# console_schematic_logic.net
KiCad netlist of a schematic drawn in Altium Designer
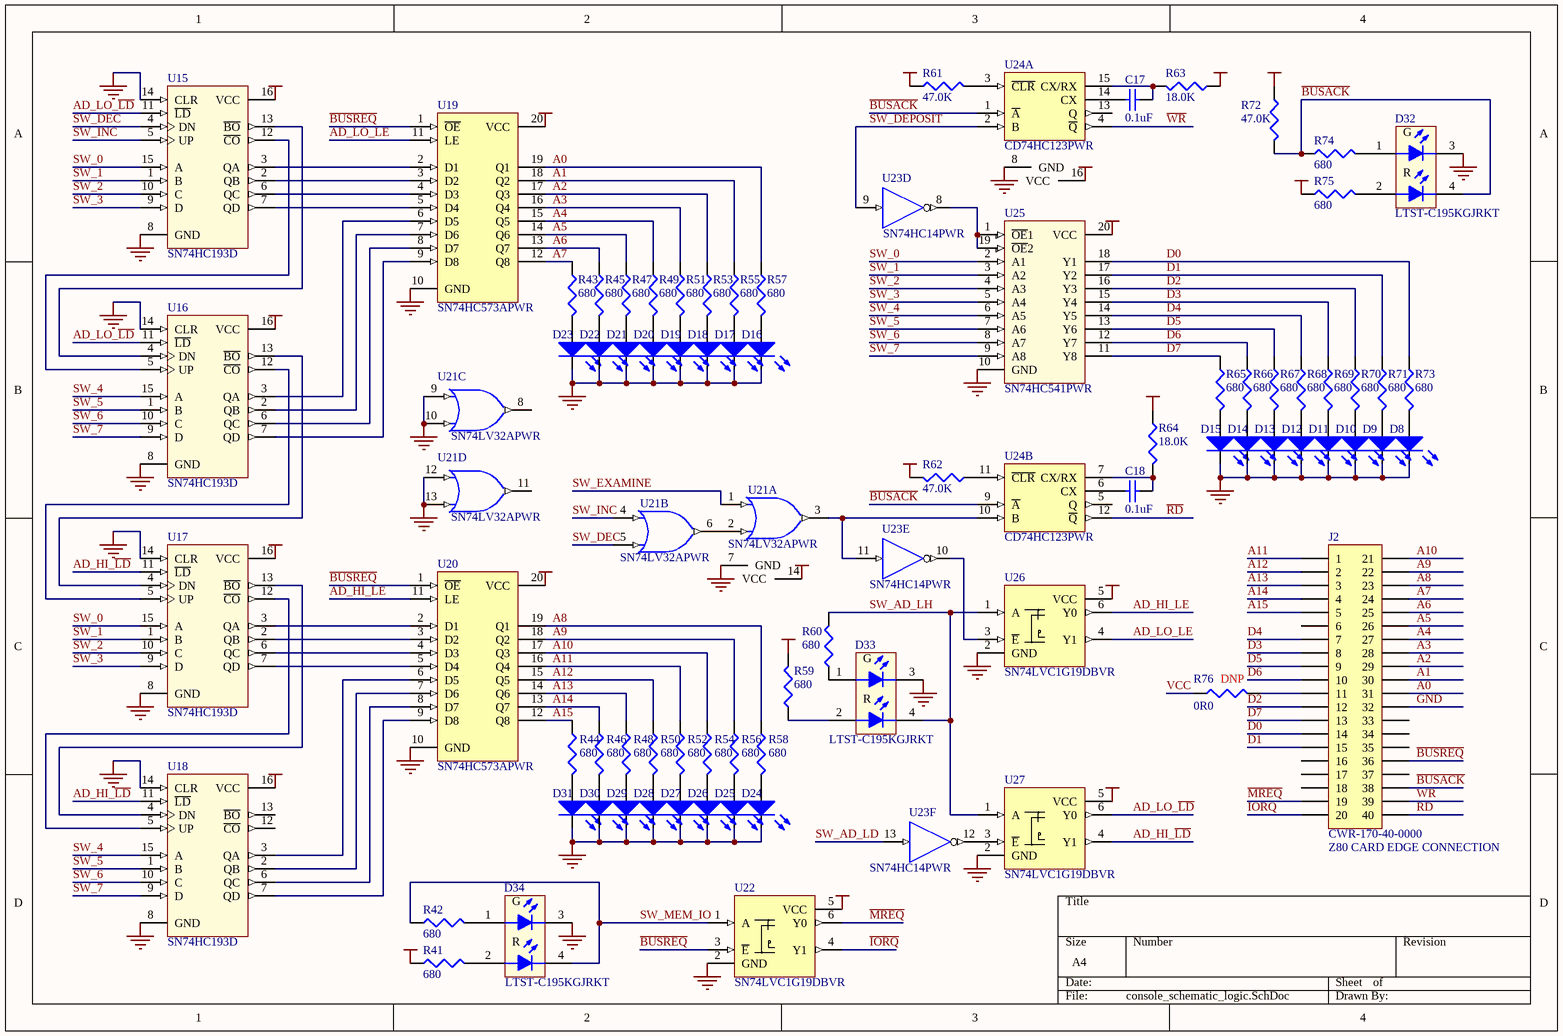
[diagram p0: console_schematic_logic.SchDoc]

(export (version "E")
  (design (tool "Eeschema 10.0.6"))
  (components
    (comp (ref "C17")
      (value "0.1uF")
      (footprint "smari_lib_pcb:0603")
      (description "CAP .10UF 16V CERAMIC X7R 0603")
      (libsource (lib "smari_lib_schematic") (part "C0603"))
    )
    (comp (ref "C18")
      (value "0.1uF")
      (footprint "smari_lib_pcb:0603")
      (description "CAP .10UF 16V CERAMIC X7R 0603")
      (libsource (lib "smari_lib_schematic") (part "C0603"))
    )
    (comp (ref "D8")
      (value "LTST-C190KRKT")
      (footprint "smari_lib_pcb:APG1608")
      (description "LED SUPER RED CLEAR 0603 SMD")
      (libsource (lib "smari_lib_schematic") (part "LTST-C190KRKT"))
    )
    (comp (ref "D9")
      (value "LTST-C190KRKT")
      (footprint "smari_lib_pcb:APG1608")
      (description "LED SUPER RED CLEAR 0603 SMD")
      (libsource (lib "smari_lib_schematic") (part "LTST-C190KRKT"))
    )
    (comp (ref "D10")
      (value "LTST-C190KRKT")
      (footprint "smari_lib_pcb:APG1608")
      (description "LED SUPER RED CLEAR 0603 SMD")
      (libsource (lib "smari_lib_schematic") (part "LTST-C190KRKT"))
    )
    (comp (ref "D11")
      (value "LTST-C190KRKT")
      (footprint "smari_lib_pcb:APG1608")
      (description "LED SUPER RED CLEAR 0603 SMD")
      (libsource (lib "smari_lib_schematic") (part "LTST-C190KRKT"))
    )
    (comp (ref "D12")
      (value "LTST-C190KRKT")
      (footprint "smari_lib_pcb:APG1608")
      (description "LED SUPER RED CLEAR 0603 SMD")
      (libsource (lib "smari_lib_schematic") (part "LTST-C190KRKT"))
    )
    (comp (ref "D13")
      (value "LTST-C190KRKT")
      (footprint "smari_lib_pcb:APG1608")
      (description "LED SUPER RED CLEAR 0603 SMD")
      (libsource (lib "smari_lib_schematic") (part "LTST-C190KRKT"))
    )
    (comp (ref "D14")
      (value "LTST-C190KRKT")
      (footprint "smari_lib_pcb:APG1608")
      (description "LED SUPER RED CLEAR 0603 SMD")
      (libsource (lib "smari_lib_schematic") (part "LTST-C190KRKT"))
    )
    (comp (ref "D15")
      (value "LTST-C190KRKT")
      (footprint "smari_lib_pcb:APG1608")
      (description "LED SUPER RED CLEAR 0603 SMD")
      (libsource (lib "smari_lib_schematic") (part "LTST-C190KRKT"))
    )
    (comp (ref "D16")
      (value "LTST-C190KRKT")
      (footprint "smari_lib_pcb:APG1608")
      (description "LED SUPER RED CLEAR 0603 SMD")
      (libsource (lib "smari_lib_schematic") (part "LTST-C190KRKT"))
    )
    (comp (ref "D17")
      (value "LTST-C190KRKT")
      (footprint "smari_lib_pcb:APG1608")
      (description "LED SUPER RED CLEAR 0603 SMD")
      (libsource (lib "smari_lib_schematic") (part "LTST-C190KRKT"))
    )
    (comp (ref "D18")
      (value "LTST-C190KRKT")
      (footprint "smari_lib_pcb:APG1608")
      (description "LED SUPER RED CLEAR 0603 SMD")
      (libsource (lib "smari_lib_schematic") (part "LTST-C190KRKT"))
    )
    (comp (ref "D19")
      (value "LTST-C190KRKT")
      (footprint "smari_lib_pcb:APG1608")
      (description "LED SUPER RED CLEAR 0603 SMD")
      (libsource (lib "smari_lib_schematic") (part "LTST-C190KRKT"))
    )
    (comp (ref "D20")
      (value "LTST-C190KRKT")
      (footprint "smari_lib_pcb:APG1608")
      (description "LED SUPER RED CLEAR 0603 SMD")
      (libsource (lib "smari_lib_schematic") (part "LTST-C190KRKT"))
    )
    (comp (ref "D21")
      (value "LTST-C190KRKT")
      (footprint "smari_lib_pcb:APG1608")
      (description "LED SUPER RED CLEAR 0603 SMD")
      (libsource (lib "smari_lib_schematic") (part "LTST-C190KRKT"))
    )
    (comp (ref "D22")
      (value "LTST-C190KRKT")
      (footprint "smari_lib_pcb:APG1608")
      (description "LED SUPER RED CLEAR 0603 SMD")
      (libsource (lib "smari_lib_schematic") (part "LTST-C190KRKT"))
    )
    (comp (ref "D23")
      (value "LTST-C190KRKT")
      (footprint "smari_lib_pcb:APG1608")
      (description "LED SUPER RED CLEAR 0603 SMD")
      (libsource (lib "smari_lib_schematic") (part "LTST-C190KRKT"))
    )
    (comp (ref "D24")
      (value "LTST-C190KRKT")
      (footprint "smari_lib_pcb:APG1608")
      (description "LED SUPER RED CLEAR 0603 SMD")
      (libsource (lib "smari_lib_schematic") (part "LTST-C190KRKT"))
    )
    (comp (ref "D25")
      (value "LTST-C190KRKT")
      (footprint "smari_lib_pcb:APG1608")
      (description "LED SUPER RED CLEAR 0603 SMD")
      (libsource (lib "smari_lib_schematic") (part "LTST-C190KRKT"))
    )
    (comp (ref "D26")
      (value "LTST-C190KRKT")
      (footprint "smari_lib_pcb:APG1608")
      (description "LED SUPER RED CLEAR 0603 SMD")
      (libsource (lib "smari_lib_schematic") (part "LTST-C190KRKT"))
    )
    (comp (ref "D27")
      (value "LTST-C190KRKT")
      (footprint "smari_lib_pcb:APG1608")
      (description "LED SUPER RED CLEAR 0603 SMD")
      (libsource (lib "smari_lib_schematic") (part "LTST-C190KRKT"))
    )
    (comp (ref "D28")
      (value "LTST-C190KRKT")
      (footprint "smari_lib_pcb:APG1608")
      (description "LED SUPER RED CLEAR 0603 SMD")
      (libsource (lib "smari_lib_schematic") (part "LTST-C190KRKT"))
    )
    (comp (ref "D29")
      (value "LTST-C190KRKT")
      (footprint "smari_lib_pcb:APG1608")
      (description "LED SUPER RED CLEAR 0603 SMD")
      (libsource (lib "smari_lib_schematic") (part "LTST-C190KRKT"))
    )
    (comp (ref "D30")
      (value "LTST-C190KRKT")
      (footprint "smari_lib_pcb:APG1608")
      (description "LED SUPER RED CLEAR 0603 SMD")
      (libsource (lib "smari_lib_schematic") (part "LTST-C190KRKT"))
    )
    (comp (ref "D31")
      (value "LTST-C190KRKT")
      (footprint "smari_lib_pcb:APG1608")
      (description "LED SUPER RED CLEAR 0603 SMD")
      (libsource (lib "smari_lib_schematic") (part "LTST-C190KRKT"))
    )
    (comp (ref "D32")
      (value "LTST-C195KGJRKT")
      (footprint "smari_lib_pcb:LTST-C195KGJRKT")
      (description "LED GREEN/RED BICOLOR 0606 SMD")
      (libsource (lib "smari_lib_schematic") (part "LTST-C195KGJRKT"))
    )
    (comp (ref "D33")
      (value "LTST-C195KGJRKT")
      (footprint "smari_lib_pcb:LTST-C195KGJRKT")
      (description "LED GREEN/RED BICOLOR 0606 SMD")
      (libsource (lib "smari_lib_schematic") (part "LTST-C195KGJRKT"))
    )
    (comp (ref "D34")
      (value "LTST-C195KGJRKT")
      (footprint "smari_lib_pcb:LTST-C195KGJRKT")
      (description "LED GREEN/RED BICOLOR 0606 SMD")
      (libsource (lib "smari_lib_schematic") (part "LTST-C195KGJRKT"))
    )
    (comp (ref "J2")
      (value "CWR-170-40-0000")
      (footprint "smari_lib_pcb:CARD EDGE 40 PIN")
      (description "CONN CARD EDGE 40PIN GOLD")
      (fields (field (name "NOTES") "Z80 CARD EDGE CONNECTION"))
      (libsource (lib "smari_lib_schematic") (part "CWR-170-40-0000"))
    )
    (comp (ref "R41")
      (value "680")
      (footprint "smari_lib_pcb:0603")
      (description "RES 680 OHM 1/10W 1% 0603 SMD")
      (libsource (lib "smari_lib_schematic") (part "MCR03EZPFX"))
    )
    (comp (ref "R42")
      (value "680")
      (footprint "smari_lib_pcb:0603")
      (description "RES 680 OHM 1/10W 1% 0603 SMD")
      (libsource (lib "smari_lib_schematic") (part "MCR03EZPFX"))
    )
    (comp (ref "R43")
      (value "680")
      (footprint "smari_lib_pcb:0603")
      (description "RES 680 OHM 1/10W 1% 0603 SMD")
      (libsource (lib "smari_lib_schematic") (part "MCR03EZPFX"))
    )
    (comp (ref "R44")
      (value "680")
      (footprint "smari_lib_pcb:0603")
      (description "RES 680 OHM 1/10W 1% 0603 SMD")
      (libsource (lib "smari_lib_schematic") (part "MCR03EZPFX"))
    )
    (comp (ref "R45")
      (value "680")
      (footprint "smari_lib_pcb:0603")
      (description "RES 680 OHM 1/10W 1% 0603 SMD")
      (libsource (lib "smari_lib_schematic") (part "MCR03EZPFX"))
    )
    (comp (ref "R46")
      (value "680")
      (footprint "smari_lib_pcb:0603")
      (description "RES 680 OHM 1/10W 1% 0603 SMD")
      (libsource (lib "smari_lib_schematic") (part "MCR03EZPFX"))
    )
    (comp (ref "R47")
      (value "680")
      (footprint "smari_lib_pcb:0603")
      (description "RES 680 OHM 1/10W 1% 0603 SMD")
      (libsource (lib "smari_lib_schematic") (part "MCR03EZPFX"))
    )
    (comp (ref "R48")
      (value "680")
      (footprint "smari_lib_pcb:0603")
      (description "RES 680 OHM 1/10W 1% 0603 SMD")
      (libsource (lib "smari_lib_schematic") (part "MCR03EZPFX"))
    )
    (comp (ref "R49")
      (value "680")
      (footprint "smari_lib_pcb:0603")
      (description "RES 680 OHM 1/10W 1% 0603 SMD")
      (libsource (lib "smari_lib_schematic") (part "MCR03EZPFX"))
    )
    (comp (ref "R50")
      (value "680")
      (footprint "smari_lib_pcb:0603")
      (description "RES 680 OHM 1/10W 1% 0603 SMD")
      (libsource (lib "smari_lib_schematic") (part "MCR03EZPFX"))
    )
    (comp (ref "R51")
      (value "680")
      (footprint "smari_lib_pcb:0603")
      (description "RES 680 OHM 1/10W 1% 0603 SMD")
      (libsource (lib "smari_lib_schematic") (part "MCR03EZPFX"))
    )
    (comp (ref "R52")
      (value "680")
      (footprint "smari_lib_pcb:0603")
      (description "RES 680 OHM 1/10W 1% 0603 SMD")
      (libsource (lib "smari_lib_schematic") (part "MCR03EZPFX"))
    )
    (comp (ref "R53")
      (value "680")
      (footprint "smari_lib_pcb:0603")
      (description "RES 680 OHM 1/10W 1% 0603 SMD")
      (libsource (lib "smari_lib_schematic") (part "MCR03EZPFX"))
    )
    (comp (ref "R54")
      (value "680")
      (footprint "smari_lib_pcb:0603")
      (description "RES 680 OHM 1/10W 1% 0603 SMD")
      (libsource (lib "smari_lib_schematic") (part "MCR03EZPFX"))
    )
    (comp (ref "R55")
      (value "680")
      (footprint "smari_lib_pcb:0603")
      (description "RES 680 OHM 1/10W 1% 0603 SMD")
      (libsource (lib "smari_lib_schematic") (part "MCR03EZPFX"))
    )
    (comp (ref "R56")
      (value "680")
      (footprint "smari_lib_pcb:0603")
      (description "RES 680 OHM 1/10W 1% 0603 SMD")
      (libsource (lib "smari_lib_schematic") (part "MCR03EZPFX"))
    )
    (comp (ref "R57")
      (value "680")
      (footprint "smari_lib_pcb:0603")
      (description "RES 680 OHM 1/10W 1% 0603 SMD")
      (libsource (lib "smari_lib_schematic") (part "MCR03EZPFX"))
    )
    (comp (ref "R58")
      (value "680")
      (footprint "smari_lib_pcb:0603")
      (description "RES 680 OHM 1/10W 1% 0603 SMD")
      (libsource (lib "smari_lib_schematic") (part "MCR03EZPFX"))
    )
    (comp (ref "R59")
      (value "680")
      (footprint "smari_lib_pcb:0603")
      (description "RES 680 OHM 1/10W 1% 0603 SMD")
      (libsource (lib "smari_lib_schematic") (part "MCR03EZPFX"))
    )
    (comp (ref "R60")
      (value "680")
      (footprint "smari_lib_pcb:0603")
      (description "RES 680 OHM 1/10W 1% 0603 SMD")
      (libsource (lib "smari_lib_schematic") (part "MCR03EZPFX"))
    )
    (comp (ref "R61")
      (value "47.0K")
      (footprint "smari_lib_pcb:0603")
      (description "RES 47.0K OHM 1/10W 1% 0603 SMD")
      (libsource (lib "smari_lib_schematic") (part "MCR03EZPFX"))
    )
    (comp (ref "R62")
      (value "47.0K")
      (footprint "smari_lib_pcb:0603")
      (description "RES 47.0K OHM 1/10W 1% 0603 SMD")
      (libsource (lib "smari_lib_schematic") (part "MCR03EZPFX"))
    )
    (comp (ref "R63")
      (value "18.0K")
      (footprint "smari_lib_pcb:0603")
      (description "RES 18.0K OHM 1/10W 1% 0603 SMD")
      (libsource (lib "smari_lib_schematic") (part "MCR03EZPFX"))
    )
    (comp (ref "R64")
      (value "18.0K")
      (footprint "smari_lib_pcb:0603")
      (description "RES 18.0K OHM 1/10W 1% 0603 SMD")
      (libsource (lib "smari_lib_schematic") (part "MCR03EZPFX"))
    )
    (comp (ref "R65")
      (value "680")
      (footprint "smari_lib_pcb:0603")
      (description "RES 680 OHM 1/10W 1% 0603 SMD")
      (libsource (lib "smari_lib_schematic") (part "MCR03EZPFX"))
    )
    (comp (ref "R66")
      (value "680")
      (footprint "smari_lib_pcb:0603")
      (description "RES 680 OHM 1/10W 1% 0603 SMD")
      (libsource (lib "smari_lib_schematic") (part "MCR03EZPFX"))
    )
    (comp (ref "R67")
      (value "680")
      (footprint "smari_lib_pcb:0603")
      (description "RES 680 OHM 1/10W 1% 0603 SMD")
      (libsource (lib "smari_lib_schematic") (part "MCR03EZPFX"))
    )
    (comp (ref "R68")
      (value "680")
      (footprint "smari_lib_pcb:0603")
      (description "RES 680 OHM 1/10W 1% 0603 SMD")
      (libsource (lib "smari_lib_schematic") (part "MCR03EZPFX"))
    )
    (comp (ref "R69")
      (value "680")
      (footprint "smari_lib_pcb:0603")
      (description "RES 680 OHM 1/10W 1% 0603 SMD")
      (libsource (lib "smari_lib_schematic") (part "MCR03EZPFX"))
    )
    (comp (ref "R70")
      (value "680")
      (footprint "smari_lib_pcb:0603")
      (description "RES 680 OHM 1/10W 1% 0603 SMD")
      (libsource (lib "smari_lib_schematic") (part "MCR03EZPFX"))
    )
    (comp (ref "R71")
      (value "680")
      (footprint "smari_lib_pcb:0603")
      (description "RES 680 OHM 1/10W 1% 0603 SMD")
      (libsource (lib "smari_lib_schematic") (part "MCR03EZPFX"))
    )
    (comp (ref "R72")
      (value "47.0K")
      (footprint "smari_lib_pcb:0603")
      (description "RES 47.0K OHM 1/10W 1% 0603 SMD")
      (libsource (lib "smari_lib_schematic") (part "MCR03EZPFX"))
    )
    (comp (ref "R73")
      (value "680")
      (footprint "smari_lib_pcb:0603")
      (description "RES 680 OHM 1/10W 1% 0603 SMD")
      (libsource (lib "smari_lib_schematic") (part "MCR03EZPFX"))
    )
    (comp (ref "R74")
      (value "680")
      (footprint "smari_lib_pcb:0603")
      (description "RES 680 OHM 1/10W 1% 0603 SMD")
      (libsource (lib "smari_lib_schematic") (part "MCR03EZPFX"))
    )
    (comp (ref "R75")
      (value "680")
      (footprint "smari_lib_pcb:0603")
      (description "RES 680 OHM 1/10W 1% 0603 SMD")
      (libsource (lib "smari_lib_schematic") (part "MCR03EZPFX"))
    )
    (comp (ref "R76")
      (value "0R0")
      (footprint "smari_lib_pcb:0603")
      (description "RES 0.0 OHM 1/10W 0603 SMD")
      (fields (field (name "LOAD") "DNP"))
      (libsource (lib "smari_lib_schematic") (part "ERJ-3EKF1002V"))
    )
    (comp (ref "U15")
      (value "SN74HC193D")
      (footprint "smari_lib_pcb:DO16 D R-PDSO-G16")
      (description "IC 4-BIT UP/DOWN COUNTER 16-SOIC")
      (libsource (lib "smari_lib_schematic") (part "SN74HC193D"))
    )
    (comp (ref "U16")
      (value "SN74HC193D")
      (footprint "smari_lib_pcb:DO16 D R-PDSO-G16")
      (description "IC 4-BIT UP/DOWN COUNTER 16-SOIC")
      (libsource (lib "smari_lib_schematic") (part "SN74HC193D"))
    )
    (comp (ref "U17")
      (value "SN74HC193D")
      (footprint "smari_lib_pcb:DO16 D R-PDSO-G16")
      (description "IC 4-BIT UP/DOWN COUNTER 16-SOIC")
      (libsource (lib "smari_lib_schematic") (part "SN74HC193D"))
    )
    (comp (ref "U18")
      (value "SN74HC193D")
      (footprint "smari_lib_pcb:DO16 D R-PDSO-G16")
      (description "IC 4-BIT UP/DOWN COUNTER 16-SOIC")
      (libsource (lib "smari_lib_schematic") (part "SN74HC193D"))
    )
    (comp (ref "U19")
      (value "SN74HC573APWR")
      (footprint "smari_lib_pcb:PW020")
      (description "IC OCTAL TRANSP LATCH 20-TSSOP")
      (libsource (lib "smari_lib_schematic") (part "SN74HC573APWR"))
    )
    (comp (ref "U20")
      (value "SN74HC573APWR")
      (footprint "smari_lib_pcb:PW020")
      (description "IC OCTAL TRANSP LATCH 20-TSSOP")
      (libsource (lib "smari_lib_schematic") (part "SN74HC573APWR"))
    )
    (comp (ref "U21")
      (value "SN74LV32APWR")
      (footprint "smari_lib_pcb:PW014")
      (description "IC QUAD 2-IN OR GATE 14-TSSOP")
      (libsource (lib "smari_lib_schematic") (part "SN74LV32APWR"))
    )
    (comp (ref "U22")
      (value "SN74LVC1G19DBVR")
      (footprint "smari_lib_pcb:SOT-23-6 DBV R-PDSO-G6")
      (description "IC MUX/DECODER SNGL 1OF2 SOT23-6")
      (libsource (lib "smari_lib_schematic") (part "SN74LVC1G19DBVR"))
    )
    (comp (ref "U23")
      (value "SN74HC14PWR")
      (footprint "smari_lib_pcb:PW014")
      (description "IC HEX SCHMITT-TRIG INV 14-TSSOP")
      (libsource (lib "smari_lib_schematic") (part "SN74HC14PWR"))
    )
    (comp (ref "U24")
      (value "CD74HC123PWR")
      (footprint "smari_lib_pcb:PW016")
      (description "IC DUAL RETRIG MULTIVIB 16-TSSOP")
      (libsource (lib "") (part "CD74HC123PWR_1"))
    )
    (comp (ref "U25")
      (value "SN74HC541PWR")
      (footprint "smari_lib_pcb:PW020")
      (description "IC BUFF/DVR TRI-ST 8BIT 20TSSOP")
      (libsource (lib "smari_lib_schematic") (part "SN74HC541PWR"))
    )
    (comp (ref "U26")
      (value "SN74LVC1G19DBVR")
      (footprint "smari_lib_pcb:SOT-23-6 DBV R-PDSO-G6")
      (description "IC MUX/DECODER SNGL 1OF2 SOT23-6")
      (libsource (lib "smari_lib_schematic") (part "SN74LVC1G19DBVR"))
    )
    (comp (ref "U27")
      (value "SN74LVC1G19DBVR")
      (footprint "smari_lib_pcb:SOT-23-6 DBV R-PDSO-G6")
      (description "IC MUX/DECODER SNGL 1OF2 SOT23-6")
      (libsource (lib "smari_lib_schematic") (part "SN74LVC1G19DBVR"))
    )
  )
  (nets
    (net (code "1") (name "/A0") (class "Default")
      (node (ref "J2") (pin "31") (pinfunction "31_31") (pintype "passive"))
      (node (ref "R57") (pin "1") (pinfunction "1_1") (pintype "passive"))
      (node (ref "U19") (pin "19") (pinfunction "Q1_19") (pintype "tri_state"))
    )
    (net (code "2") (name "/A1") (class "Default")
      (node (ref "J2") (pin "30") (pinfunction "30_30") (pintype "passive"))
      (node (ref "R55") (pin "1") (pinfunction "1_1") (pintype "passive"))
      (node (ref "U19") (pin "18") (pinfunction "Q2_18") (pintype "tri_state"))
    )
    (net (code "3") (name "/A2") (class "Default")
      (node (ref "J2") (pin "29") (pinfunction "29_29") (pintype "passive"))
      (node (ref "R53") (pin "1") (pinfunction "1_1") (pintype "passive"))
      (node (ref "U19") (pin "17") (pinfunction "Q3_17") (pintype "tri_state"))
    )
    (net (code "4") (name "/A3") (class "Default")
      (node (ref "J2") (pin "28") (pinfunction "28_28") (pintype "passive"))
      (node (ref "R51") (pin "1") (pinfunction "1_1") (pintype "passive"))
      (node (ref "U19") (pin "16") (pinfunction "Q4_16") (pintype "tri_state"))
    )
    (net (code "5") (name "/A4") (class "Default")
      (node (ref "J2") (pin "27") (pinfunction "27_27") (pintype "passive"))
      (node (ref "R49") (pin "1") (pinfunction "1_1") (pintype "passive"))
      (node (ref "U19") (pin "15") (pinfunction "Q5_15") (pintype "tri_state"))
    )
    (net (code "6") (name "/A5") (class "Default")
      (node (ref "J2") (pin "26") (pinfunction "26_26") (pintype "passive"))
      (node (ref "R47") (pin "1") (pinfunction "1_1") (pintype "passive"))
      (node (ref "U19") (pin "14") (pinfunction "Q6_14") (pintype "tri_state"))
    )
    (net (code "7") (name "/A6") (class "Default")
      (node (ref "J2") (pin "25") (pinfunction "25_25") (pintype "passive"))
      (node (ref "R45") (pin "1") (pinfunction "1_1") (pintype "passive"))
      (node (ref "U19") (pin "13") (pinfunction "Q7_13") (pintype "tri_state"))
    )
    (net (code "8") (name "/A7") (class "Default")
      (node (ref "J2") (pin "24") (pinfunction "24_24") (pintype "passive"))
      (node (ref "R43") (pin "1") (pinfunction "1_1") (pintype "passive"))
      (node (ref "U19") (pin "12") (pinfunction "Q8_12") (pintype "tri_state"))
    )
    (net (code "9") (name "/A8") (class "Default")
      (node (ref "J2") (pin "23") (pinfunction "23_23") (pintype "passive"))
      (node (ref "R58") (pin "1") (pinfunction "1_1") (pintype "passive"))
      (node (ref "U20") (pin "19") (pinfunction "Q1_19") (pintype "tri_state"))
    )
    (net (code "10") (name "/A9") (class "Default")
      (node (ref "J2") (pin "22") (pinfunction "22_22") (pintype "passive"))
      (node (ref "R56") (pin "1") (pinfunction "1_1") (pintype "passive"))
      (node (ref "U20") (pin "18") (pinfunction "Q2_18") (pintype "tri_state"))
    )
    (net (code "11") (name "/A10") (class "Default")
      (node (ref "J2") (pin "21") (pinfunction "21_21") (pintype "passive"))
      (node (ref "R54") (pin "1") (pinfunction "1_1") (pintype "passive"))
      (node (ref "U20") (pin "17") (pinfunction "Q3_17") (pintype "tri_state"))
    )
    (net (code "12") (name "/A11") (class "Default")
      (node (ref "J2") (pin "1") (pinfunction "1_1") (pintype "passive"))
      (node (ref "R52") (pin "1") (pinfunction "1_1") (pintype "passive"))
      (node (ref "U20") (pin "16") (pinfunction "Q4_16") (pintype "tri_state"))
    )
    (net (code "13") (name "/A12") (class "Default")
      (node (ref "J2") (pin "2") (pinfunction "2_2") (pintype "passive"))
      (node (ref "R50") (pin "1") (pinfunction "1_1") (pintype "passive"))
      (node (ref "U20") (pin "15") (pinfunction "Q5_15") (pintype "tri_state"))
    )
    (net (code "14") (name "/A13") (class "Default")
      (node (ref "J2") (pin "3") (pinfunction "3_3") (pintype "passive"))
      (node (ref "R48") (pin "1") (pinfunction "1_1") (pintype "passive"))
      (node (ref "U20") (pin "14") (pinfunction "Q6_14") (pintype "tri_state"))
    )
    (net (code "15") (name "/A14") (class "Default")
      (node (ref "J2") (pin "4") (pinfunction "4_4") (pintype "passive"))
      (node (ref "R46") (pin "1") (pinfunction "1_1") (pintype "passive"))
      (node (ref "U20") (pin "13") (pinfunction "Q7_13") (pintype "tri_state"))
    )
    (net (code "16") (name "/A15") (class "Default")
      (node (ref "J2") (pin "5") (pinfunction "5_5") (pintype "passive"))
      (node (ref "R44") (pin "1") (pinfunction "1_1") (pintype "passive"))
      (node (ref "U20") (pin "12") (pinfunction "Q8_12") (pintype "tri_state"))
    )
    (net (code "17") (name "/AD_HI_LE") (class "Default")
      (node (ref "U20") (pin "11") (pinfunction "LE_11") (pintype "input"))
      (node (ref "U26") (pin "6") (pinfunction "Y0_6") (pintype "output"))
    )
    (net (code "18") (name "/AD_HI_~{LD}") (class "Default")
      (node (ref "U17") (pin "11") (pinfunction "~{LD}_11") (pintype "input"))
      (node (ref "U18") (pin "11") (pinfunction "~{LD}_11") (pintype "input"))
      (node (ref "U27") (pin "4") (pinfunction "Y1_4") (pintype "output"))
    )
    (net (code "19") (name "/AD_LO_LE") (class "Default")
      (node (ref "U19") (pin "11") (pinfunction "LE_11") (pintype "input"))
      (node (ref "U26") (pin "4") (pinfunction "Y1_4") (pintype "output"))
    )
    (net (code "20") (name "/AD_LO_~{LD}") (class "Default")
      (node (ref "U15") (pin "11") (pinfunction "~{LD}_11") (pintype "input"))
      (node (ref "U16") (pin "11") (pinfunction "~{LD}_11") (pintype "input"))
      (node (ref "U27") (pin "6") (pinfunction "Y0_6") (pintype "output"))
    )
    (net (code "21") (name "/D0") (class "Default")
      (node (ref "J2") (pin "14") (pinfunction "14_14") (pintype "passive"))
      (node (ref "R73") (pin "1") (pinfunction "1_1") (pintype "passive"))
      (node (ref "U25") (pin "18") (pinfunction "Y1_18") (pintype "tri_state"))
    )
    (net (code "22") (name "/D1") (class "Default")
      (node (ref "J2") (pin "15") (pinfunction "15_15") (pintype "passive"))
      (node (ref "R71") (pin "1") (pinfunction "1_1") (pintype "passive"))
      (node (ref "U25") (pin "17") (pinfunction "Y2_17") (pintype "tri_state"))
    )
    (net (code "23") (name "/D2") (class "Default")
      (node (ref "J2") (pin "12") (pinfunction "12_12") (pintype "passive"))
      (node (ref "R70") (pin "1") (pinfunction "1_1") (pintype "passive"))
      (node (ref "U25") (pin "16") (pinfunction "Y3_16") (pintype "tri_state"))
    )
    (net (code "24") (name "/D3") (class "Default")
      (node (ref "J2") (pin "8") (pinfunction "8_8") (pintype "passive"))
      (node (ref "R69") (pin "1") (pinfunction "1_1") (pintype "passive"))
      (node (ref "U25") (pin "15") (pinfunction "Y4_15") (pintype "tri_state"))
    )
    (net (code "25") (name "/D4") (class "Default")
      (node (ref "J2") (pin "7") (pinfunction "7_7") (pintype "passive"))
      (node (ref "R68") (pin "1") (pinfunction "1_1") (pintype "passive"))
      (node (ref "U25") (pin "14") (pinfunction "Y5_14") (pintype "tri_state"))
    )
    (net (code "26") (name "/D5") (class "Default")
      (node (ref "J2") (pin "9") (pinfunction "9_9") (pintype "passive"))
      (node (ref "R67") (pin "1") (pinfunction "1_1") (pintype "passive"))
      (node (ref "U25") (pin "13") (pinfunction "Y6_13") (pintype "tri_state"))
    )
    (net (code "27") (name "/D6") (class "Default")
      (node (ref "J2") (pin "10") (pinfunction "10_10") (pintype "passive"))
      (node (ref "R66") (pin "1") (pinfunction "1_1") (pintype "passive"))
      (node (ref "U25") (pin "12") (pinfunction "Y7_12") (pintype "tri_state"))
    )
    (net (code "28") (name "/D7") (class "Default")
      (node (ref "J2") (pin "13") (pinfunction "13_13") (pintype "passive"))
      (node (ref "R65") (pin "1") (pinfunction "1_1") (pintype "passive"))
      (node (ref "U25") (pin "11") (pinfunction "Y8_11") (pintype "tri_state"))
    )
    (net (code "29") (name "/SW_0") (class "Default")
      (node (ref "U15") (pin "15") (pinfunction "A_15") (pintype "input"))
      (node (ref "U17") (pin "15") (pinfunction "A_15") (pintype "input"))
      (node (ref "U25") (pin "2") (pinfunction "A1_2") (pintype "input"))
    )
    (net (code "30") (name "/SW_1") (class "Default")
      (node (ref "U15") (pin "1") (pinfunction "B_1") (pintype "input"))
      (node (ref "U17") (pin "1") (pinfunction "B_1") (pintype "input"))
      (node (ref "U25") (pin "3") (pinfunction "A2_3") (pintype "input"))
    )
    (net (code "31") (name "/SW_2") (class "Default")
      (node (ref "U15") (pin "10") (pinfunction "C_10") (pintype "input"))
      (node (ref "U17") (pin "10") (pinfunction "C_10") (pintype "input"))
      (node (ref "U25") (pin "4") (pinfunction "A3_4") (pintype "input"))
    )
    (net (code "32") (name "/SW_3") (class "Default")
      (node (ref "U15") (pin "9") (pinfunction "D_9") (pintype "input"))
      (node (ref "U17") (pin "9") (pinfunction "D_9") (pintype "input"))
      (node (ref "U25") (pin "5") (pinfunction "A4_5") (pintype "input"))
    )
    (net (code "33") (name "/SW_4") (class "Default")
      (node (ref "U16") (pin "15") (pinfunction "A_15") (pintype "input"))
      (node (ref "U18") (pin "15") (pinfunction "A_15") (pintype "input"))
      (node (ref "U25") (pin "6") (pinfunction "A5_6") (pintype "input"))
    )
    (net (code "34") (name "/SW_5") (class "Default")
      (node (ref "U16") (pin "1") (pinfunction "B_1") (pintype "input"))
      (node (ref "U18") (pin "1") (pinfunction "B_1") (pintype "input"))
      (node (ref "U25") (pin "7") (pinfunction "A6_7") (pintype "input"))
    )
    (net (code "35") (name "/SW_6") (class "Default")
      (node (ref "U16") (pin "10") (pinfunction "C_10") (pintype "input"))
      (node (ref "U18") (pin "10") (pinfunction "C_10") (pintype "input"))
      (node (ref "U25") (pin "8") (pinfunction "A7_8") (pintype "input"))
    )
    (net (code "36") (name "/SW_7") (class "Default")
      (node (ref "U16") (pin "9") (pinfunction "D_9") (pintype "input"))
      (node (ref "U18") (pin "9") (pinfunction "D_9") (pintype "input"))
      (node (ref "U25") (pin "9") (pinfunction "A8_9") (pintype "input"))
    )
    (net (code "37") (name "/SW_AD_LD") (class "Default")
      (node (ref "U23") (pin "13") (pinfunction "A_13") (pintype "input"))
    )
    (net (code "38") (name "/SW_AD_LH") (class "Default")
      (node (ref "D33") (pin "4") (pinfunction "K2_4") (pintype "passive"))
      (node (ref "R60") (pin "2") (pinfunction "2_2") (pintype "passive"))
      (node (ref "U26") (pin "1") (pinfunction "A_1") (pintype "input"))
      (node (ref "U27") (pin "1") (pinfunction "A_1") (pintype "input"))
    )
    (net (code "39") (name "/SW_DEC") (class "Default")
      (node (ref "U15") (pin "4") (pinfunction "DN_4") (pintype "input"))
      (node (ref "U21") (pin "5") (pinfunction "B_5") (pintype "input"))
    )
    (net (code "40") (name "/SW_DEPOSIT") (class "Default")
      (node (ref "U23") (pin "9") (pinfunction "A_9") (pintype "input"))
      (node (ref "U24") (pin "2") (pinfunction "B_2") (pintype "input"))
    )
    (net (code "41") (name "/SW_EXAMINE") (class "Default")
      (node (ref "U21") (pin "1") (pinfunction "A_1") (pintype "input"))
    )
    (net (code "42") (name "/SW_INC") (class "Default")
      (node (ref "U15") (pin "5") (pinfunction "UP_5") (pintype "input"))
      (node (ref "U21") (pin "4") (pinfunction "A_4") (pintype "input"))
    )
    (net (code "43") (name "/SW_MEM_IO") (class "Default")
      (node (ref "D34") (pin "4") (pinfunction "K2_4") (pintype "passive"))
      (node (ref "R42") (pin "1") (pinfunction "1_1") (pintype "passive"))
      (node (ref "U22") (pin "1") (pinfunction "A_1") (pintype "input"))
    )
    (net (code "44") (name "/~{BUSACK}") (class "Default")
      (node (ref "D32") (pin "4") (pinfunction "K2_4") (pintype "passive"))
      (node (ref "J2") (pin "38") (pinfunction "38_38") (pintype "passive"))
      (node (ref "R72") (pin "2") (pinfunction "2_2") (pintype "passive"))
      (node (ref "R74") (pin "1") (pinfunction "1_1") (pintype "passive"))
      (node (ref "U24") (pin "1") (pinfunction "~{A}_1") (pintype "input"))
      (node (ref "U24") (pin "9") (pinfunction "~{A}_9") (pintype "input"))
    )
    (net (code "45") (name "/~{BUSREQ}") (class "Default")
      (node (ref "J2") (pin "36") (pinfunction "36_36") (pintype "passive"))
      (node (ref "U19") (pin "1") (pinfunction "~{OE}_1") (pintype "input"))
      (node (ref "U20") (pin "1") (pinfunction "~{OE}_1") (pintype "input"))
      (node (ref "U22") (pin "3") (pinfunction "~{E}_3") (pintype "input"))
    )
    (net (code "46") (name "/~{IORQ}") (class "Default")
      (node (ref "J2") (pin "20") (pinfunction "20_20") (pintype "passive"))
      (node (ref "U22") (pin "4") (pinfunction "Y1_4") (pintype "output"))
    )
    (net (code "47") (name "/~{MREQ}") (class "Default")
      (node (ref "J2") (pin "19") (pinfunction "19_19") (pintype "passive"))
      (node (ref "U22") (pin "6") (pinfunction "Y0_6") (pintype "output"))
    )
    (net (code "48") (name "/~{RD}") (class "Default")
      (node (ref "J2") (pin "40") (pinfunction "40_40") (pintype "passive"))
      (node (ref "U24") (pin "12") (pinfunction "~{Q}_12") (pintype "output"))
    )
    (net (code "49") (name "/~{WR}") (class "Default")
      (node (ref "J2") (pin "39") (pinfunction "39_39") (pintype "passive"))
      (node (ref "U24") (pin "4") (pinfunction "~{Q}_4") (pintype "output"))
    )
    (net (code "50") (name "GND") (class "Default")
      (node (ref "D10") (pin "2") (pinfunction "K_2") (pintype "passive"))
      (node (ref "D11") (pin "2") (pinfunction "K_2") (pintype "passive"))
      (node (ref "D12") (pin "2") (pinfunction "K_2") (pintype "passive"))
      (node (ref "D13") (pin "2") (pinfunction "K_2") (pintype "passive"))
      (node (ref "D14") (pin "2") (pinfunction "K_2") (pintype "passive"))
      (node (ref "D15") (pin "2") (pinfunction "K_2") (pintype "passive"))
      (node (ref "D16") (pin "2") (pinfunction "K_2") (pintype "passive"))
      (node (ref "D17") (pin "2") (pinfunction "K_2") (pintype "passive"))
      (node (ref "D18") (pin "2") (pinfunction "K_2") (pintype "passive"))
      (node (ref "D19") (pin "2") (pinfunction "K_2") (pintype "passive"))
      (node (ref "D20") (pin "2") (pinfunction "K_2") (pintype "passive"))
      (node (ref "D21") (pin "2") (pinfunction "K_2") (pintype "passive"))
      (node (ref "D22") (pin "2") (pinfunction "K_2") (pintype "passive"))
      (node (ref "D23") (pin "2") (pinfunction "K_2") (pintype "passive"))
      (node (ref "D24") (pin "2") (pinfunction "K_2") (pintype "passive"))
      (node (ref "D25") (pin "2") (pinfunction "K_2") (pintype "passive"))
      (node (ref "D26") (pin "2") (pinfunction "K_2") (pintype "passive"))
      (node (ref "D27") (pin "2") (pinfunction "K_2") (pintype "passive"))
      (node (ref "D28") (pin "2") (pinfunction "K_2") (pintype "passive"))
      (node (ref "D29") (pin "2") (pinfunction "K_2") (pintype "passive"))
      (node (ref "D30") (pin "2") (pinfunction "K_2") (pintype "passive"))
      (node (ref "D31") (pin "2") (pinfunction "K_2") (pintype "passive"))
      (node (ref "D32") (pin "3") (pinfunction "K1_3") (pintype "passive"))
      (node (ref "D33") (pin "3") (pinfunction "K1_3") (pintype "passive"))
      (node (ref "D34") (pin "3") (pinfunction "K1_3") (pintype "passive"))
      (node (ref "D8") (pin "2") (pinfunction "K_2") (pintype "passive"))
      (node (ref "D9") (pin "2") (pinfunction "K_2") (pintype "passive"))
      (node (ref "J2") (pin "32") (pinfunction "32_32") (pintype "passive"))
      (node (ref "U15") (pin "14") (pinfunction "CLR_14") (pintype "input"))
      (node (ref "U15") (pin "8") (pinfunction "GND_8") (pintype "power_in"))
      (node (ref "U16") (pin "14") (pinfunction "CLR_14") (pintype "input"))
      (node (ref "U16") (pin "8") (pinfunction "GND_8") (pintype "power_in"))
      (node (ref "U17") (pin "14") (pinfunction "CLR_14") (pintype "input"))
      (node (ref "U17") (pin "8") (pinfunction "GND_8") (pintype "power_in"))
      (node (ref "U18") (pin "14") (pinfunction "CLR_14") (pintype "input"))
      (node (ref "U18") (pin "8") (pinfunction "GND_8") (pintype "power_in"))
      (node (ref "U19") (pin "10") (pinfunction "GND_10") (pintype "power_in"))
      (node (ref "U20") (pin "10") (pinfunction "GND_10") (pintype "power_in"))
      (node (ref "U21") (pin "10") (pinfunction "B_10") (pintype "input"))
      (node (ref "U21") (pin "12") (pinfunction "A_12") (pintype "input"))
      (node (ref "U21") (pin "13") (pinfunction "B_13") (pintype "input"))
      (node (ref "U21") (pin "7") (pinfunction "GND_7") (pintype "power_in"))
      (node (ref "U21") (pin "9") (pinfunction "A_9") (pintype "input"))
      (node (ref "U22") (pin "2") (pinfunction "GND_2") (pintype "power_in"))
      (node (ref "U23") (pin "7") (pinfunction "GND_7") (pintype "power_in"))
      (node (ref "U24") (pin "8") (pinfunction "GND_8") (pintype "power_in"))
      (node (ref "U25") (pin "10") (pinfunction "GND_10") (pintype "power_in"))
      (node (ref "U26") (pin "2") (pinfunction "GND_2") (pintype "power_in"))
      (node (ref "U27") (pin "2") (pinfunction "GND_2") (pintype "power_in"))
    )
    (net (code "51") (name "Net-(D8-A)") (class "Default")
      (node (ref "D8") (pin "1") (pinfunction "A_1") (pintype "passive"))
      (node (ref "R73") (pin "2") (pinfunction "2_2") (pintype "passive"))
    )
    (net (code "52") (name "Net-(D9-A)") (class "Default")
      (node (ref "D9") (pin "1") (pinfunction "A_1") (pintype "passive"))
      (node (ref "R71") (pin "2") (pinfunction "2_2") (pintype "passive"))
    )
    (net (code "53") (name "Net-(D10-A)") (class "Default")
      (node (ref "D10") (pin "1") (pinfunction "A_1") (pintype "passive"))
      (node (ref "R70") (pin "2") (pinfunction "2_2") (pintype "passive"))
    )
    (net (code "54") (name "Net-(D11-A)") (class "Default")
      (node (ref "D11") (pin "1") (pinfunction "A_1") (pintype "passive"))
      (node (ref "R69") (pin "2") (pinfunction "2_2") (pintype "passive"))
    )
    (net (code "55") (name "Net-(D12-A)") (class "Default")
      (node (ref "D12") (pin "1") (pinfunction "A_1") (pintype "passive"))
      (node (ref "R68") (pin "2") (pinfunction "2_2") (pintype "passive"))
    )
    (net (code "56") (name "Net-(D13-A)") (class "Default")
      (node (ref "D13") (pin "1") (pinfunction "A_1") (pintype "passive"))
      (node (ref "R67") (pin "2") (pinfunction "2_2") (pintype "passive"))
    )
    (net (code "57") (name "Net-(D14-A)") (class "Default")
      (node (ref "D14") (pin "1") (pinfunction "A_1") (pintype "passive"))
      (node (ref "R66") (pin "2") (pinfunction "2_2") (pintype "passive"))
    )
    (net (code "58") (name "Net-(D15-A)") (class "Default")
      (node (ref "D15") (pin "1") (pinfunction "A_1") (pintype "passive"))
      (node (ref "R65") (pin "2") (pinfunction "2_2") (pintype "passive"))
    )
    (net (code "59") (name "Net-(D16-A)") (class "Default")
      (node (ref "D16") (pin "1") (pinfunction "A_1") (pintype "passive"))
      (node (ref "R57") (pin "2") (pinfunction "2_2") (pintype "passive"))
    )
    (net (code "60") (name "Net-(D17-A)") (class "Default")
      (node (ref "D17") (pin "1") (pinfunction "A_1") (pintype "passive"))
      (node (ref "R55") (pin "2") (pinfunction "2_2") (pintype "passive"))
    )
    (net (code "61") (name "Net-(D18-A)") (class "Default")
      (node (ref "D18") (pin "1") (pinfunction "A_1") (pintype "passive"))
      (node (ref "R53") (pin "2") (pinfunction "2_2") (pintype "passive"))
    )
    (net (code "62") (name "Net-(D19-A)") (class "Default")
      (node (ref "D19") (pin "1") (pinfunction "A_1") (pintype "passive"))
      (node (ref "R51") (pin "2") (pinfunction "2_2") (pintype "passive"))
    )
    (net (code "63") (name "Net-(D20-A)") (class "Default")
      (node (ref "D20") (pin "1") (pinfunction "A_1") (pintype "passive"))
      (node (ref "R49") (pin "2") (pinfunction "2_2") (pintype "passive"))
    )
    (net (code "64") (name "Net-(D21-A)") (class "Default")
      (node (ref "D21") (pin "1") (pinfunction "A_1") (pintype "passive"))
      (node (ref "R47") (pin "2") (pinfunction "2_2") (pintype "passive"))
    )
    (net (code "65") (name "Net-(D22-A)") (class "Default")
      (node (ref "D22") (pin "1") (pinfunction "A_1") (pintype "passive"))
      (node (ref "R45") (pin "2") (pinfunction "2_2") (pintype "passive"))
    )
    (net (code "66") (name "Net-(D23-A)") (class "Default")
      (node (ref "D23") (pin "1") (pinfunction "A_1") (pintype "passive"))
      (node (ref "R43") (pin "2") (pinfunction "2_2") (pintype "passive"))
    )
    (net (code "67") (name "Net-(D24-A)") (class "Default")
      (node (ref "D24") (pin "1") (pinfunction "A_1") (pintype "passive"))
      (node (ref "R58") (pin "2") (pinfunction "2_2") (pintype "passive"))
    )
    (net (code "68") (name "Net-(D25-A)") (class "Default")
      (node (ref "D25") (pin "1") (pinfunction "A_1") (pintype "passive"))
      (node (ref "R56") (pin "2") (pinfunction "2_2") (pintype "passive"))
    )
    (net (code "69") (name "Net-(D26-A)") (class "Default")
      (node (ref "D26") (pin "1") (pinfunction "A_1") (pintype "passive"))
      (node (ref "R54") (pin "2") (pinfunction "2_2") (pintype "passive"))
    )
    (net (code "70") (name "Net-(D27-A)") (class "Default")
      (node (ref "D27") (pin "1") (pinfunction "A_1") (pintype "passive"))
      (node (ref "R52") (pin "2") (pinfunction "2_2") (pintype "passive"))
    )
    (net (code "71") (name "Net-(D28-A)") (class "Default")
      (node (ref "D28") (pin "1") (pinfunction "A_1") (pintype "passive"))
      (node (ref "R50") (pin "2") (pinfunction "2_2") (pintype "passive"))
    )
    (net (code "72") (name "Net-(D29-A)") (class "Default")
      (node (ref "D29") (pin "1") (pinfunction "A_1") (pintype "passive"))
      (node (ref "R48") (pin "2") (pinfunction "2_2") (pintype "passive"))
    )
    (net (code "73") (name "Net-(D30-A)") (class "Default")
      (node (ref "D30") (pin "1") (pinfunction "A_1") (pintype "passive"))
      (node (ref "R46") (pin "2") (pinfunction "2_2") (pintype "passive"))
    )
    (net (code "74") (name "Net-(D31-A)") (class "Default")
      (node (ref "D31") (pin "1") (pinfunction "A_1") (pintype "passive"))
      (node (ref "R44") (pin "2") (pinfunction "2_2") (pintype "passive"))
    )
    (net (code "75") (name "Net-(D32-A1)") (class "Default")
      (node (ref "D32") (pin "1") (pinfunction "A1_1") (pintype "passive"))
      (node (ref "R74") (pin "2") (pinfunction "2_2") (pintype "passive"))
    )
    (net (code "76") (name "Net-(D32-A2)") (class "Default")
      (node (ref "D32") (pin "2") (pinfunction "A2_2") (pintype "passive"))
      (node (ref "R75") (pin "2") (pinfunction "2_2") (pintype "passive"))
    )
    (net (code "77") (name "Net-(D33-A1)") (class "Default")
      (node (ref "D33") (pin "1") (pinfunction "A1_1") (pintype "passive"))
      (node (ref "R60") (pin "1") (pinfunction "1_1") (pintype "passive"))
    )
    (net (code "78") (name "Net-(D33-A2)") (class "Default")
      (node (ref "D33") (pin "2") (pinfunction "A2_2") (pintype "passive"))
      (node (ref "R59") (pin "1") (pinfunction "1_1") (pintype "passive"))
    )
    (net (code "79") (name "Net-(D34-A1)") (class "Default")
      (node (ref "D34") (pin "1") (pinfunction "A1_1") (pintype "passive"))
      (node (ref "R42") (pin "2") (pinfunction "2_2") (pintype "passive"))
    )
    (net (code "80") (name "Net-(D34-A2)") (class "Default")
      (node (ref "D34") (pin "2") (pinfunction "A2_2") (pintype "passive"))
      (node (ref "R41") (pin "2") (pinfunction "2_2") (pintype "passive"))
    )
    (net (code "81") (name "Net-(J2-Pad11)") (class "Default")
      (node (ref "J2") (pin "11") (pinfunction "11_11") (pintype "passive"))
      (node (ref "R76") (pin "2") (pinfunction "2_2") (pintype "passive"))
    )
    (net (code "82") (name "Net-(U15-QA)") (class "Default")
      (node (ref "U15") (pin "3") (pinfunction "QA_3") (pintype "output"))
      (node (ref "U19") (pin "2") (pinfunction "D1_2") (pintype "input"))
    )
    (net (code "83") (name "Net-(U15-QB)") (class "Default")
      (node (ref "U15") (pin "2") (pinfunction "QB_2") (pintype "output"))
      (node (ref "U19") (pin "3") (pinfunction "D2_3") (pintype "input"))
    )
    (net (code "84") (name "Net-(U15-QC)") (class "Default")
      (node (ref "U15") (pin "6") (pinfunction "QC_6") (pintype "output"))
      (node (ref "U19") (pin "4") (pinfunction "D3_4") (pintype "input"))
    )
    (net (code "85") (name "Net-(U15-QD)") (class "Default")
      (node (ref "U15") (pin "7") (pinfunction "QD_7") (pintype "output"))
      (node (ref "U19") (pin "5") (pinfunction "D4_5") (pintype "input"))
    )
    (net (code "86") (name "Net-(U15-~{BO})") (class "Default")
      (node (ref "U15") (pin "13") (pinfunction "~{BO}_13") (pintype "output"))
      (node (ref "U16") (pin "4") (pinfunction "DN_4") (pintype "input"))
    )
    (net (code "87") (name "Net-(U15-~{CO})") (class "Default")
      (node (ref "U15") (pin "12") (pinfunction "~{CO}_12") (pintype "output"))
      (node (ref "U16") (pin "5") (pinfunction "UP_5") (pintype "input"))
    )
    (net (code "88") (name "Net-(U16-QA)") (class "Default")
      (node (ref "U16") (pin "3") (pinfunction "QA_3") (pintype "output"))
      (node (ref "U19") (pin "6") (pinfunction "D5_6") (pintype "input"))
    )
    (net (code "89") (name "Net-(U16-QB)") (class "Default")
      (node (ref "U16") (pin "2") (pinfunction "QB_2") (pintype "output"))
      (node (ref "U19") (pin "7") (pinfunction "D6_7") (pintype "input"))
    )
    (net (code "90") (name "Net-(U16-QC)") (class "Default")
      (node (ref "U16") (pin "6") (pinfunction "QC_6") (pintype "output"))
      (node (ref "U19") (pin "8") (pinfunction "D7_8") (pintype "input"))
    )
    (net (code "91") (name "Net-(U16-QD)") (class "Default")
      (node (ref "U16") (pin "7") (pinfunction "QD_7") (pintype "output"))
      (node (ref "U19") (pin "9") (pinfunction "D8_9") (pintype "input"))
    )
    (net (code "92") (name "Net-(U16-~{BO})") (class "Default")
      (node (ref "U16") (pin "13") (pinfunction "~{BO}_13") (pintype "output"))
      (node (ref "U17") (pin "4") (pinfunction "DN_4") (pintype "input"))
    )
    (net (code "93") (name "Net-(U16-~{CO})") (class "Default")
      (node (ref "U16") (pin "12") (pinfunction "~{CO}_12") (pintype "output"))
      (node (ref "U17") (pin "5") (pinfunction "UP_5") (pintype "input"))
    )
    (net (code "94") (name "Net-(U17-QA)") (class "Default")
      (node (ref "U17") (pin "3") (pinfunction "QA_3") (pintype "output"))
      (node (ref "U20") (pin "2") (pinfunction "D1_2") (pintype "input"))
    )
    (net (code "95") (name "Net-(U17-QB)") (class "Default")
      (node (ref "U17") (pin "2") (pinfunction "QB_2") (pintype "output"))
      (node (ref "U20") (pin "3") (pinfunction "D2_3") (pintype "input"))
    )
    (net (code "96") (name "Net-(U17-QC)") (class "Default")
      (node (ref "U17") (pin "6") (pinfunction "QC_6") (pintype "output"))
      (node (ref "U20") (pin "4") (pinfunction "D3_4") (pintype "input"))
    )
    (net (code "97") (name "Net-(U17-QD)") (class "Default")
      (node (ref "U17") (pin "7") (pinfunction "QD_7") (pintype "output"))
      (node (ref "U20") (pin "5") (pinfunction "D4_5") (pintype "input"))
    )
    (net (code "98") (name "Net-(U17-~{BO})") (class "Default")
      (node (ref "U17") (pin "13") (pinfunction "~{BO}_13") (pintype "output"))
      (node (ref "U18") (pin "4") (pinfunction "DN_4") (pintype "input"))
    )
    (net (code "99") (name "Net-(U17-~{CO})") (class "Default")
      (node (ref "U17") (pin "12") (pinfunction "~{CO}_12") (pintype "output"))
      (node (ref "U18") (pin "5") (pinfunction "UP_5") (pintype "input"))
    )
    (net (code "100") (name "Net-(U18-QA)") (class "Default")
      (node (ref "U18") (pin "3") (pinfunction "QA_3") (pintype "output"))
      (node (ref "U20") (pin "6") (pinfunction "D5_6") (pintype "input"))
    )
    (net (code "101") (name "Net-(U18-QB)") (class "Default")
      (node (ref "U18") (pin "2") (pinfunction "QB_2") (pintype "output"))
      (node (ref "U20") (pin "7") (pinfunction "D6_7") (pintype "input"))
    )
    (net (code "102") (name "Net-(U18-QC)") (class "Default")
      (node (ref "U18") (pin "6") (pinfunction "QC_6") (pintype "output"))
      (node (ref "U20") (pin "8") (pinfunction "D7_8") (pintype "input"))
    )
    (net (code "103") (name "Net-(U18-QD)") (class "Default")
      (node (ref "U18") (pin "7") (pinfunction "QD_7") (pintype "output"))
      (node (ref "U20") (pin "9") (pinfunction "D8_9") (pintype "input"))
    )
    (net (code "104") (name "Net-(U21A-B)") (class "Default")
      (node (ref "U21") (pin "2") (pinfunction "B_2") (pintype "input"))
      (node (ref "U21") (pin "6") (pinfunction "Y_6") (pintype "output"))
    )
    (net (code "105") (name "Net-(U21A-Y)") (class "Default")
      (node (ref "U21") (pin "3") (pinfunction "Y_3") (pintype "output"))
      (node (ref "U23") (pin "11") (pinfunction "A_11") (pintype "input"))
      (node (ref "U24") (pin "10") (pinfunction "B_10") (pintype "input"))
    )
    (net (code "106") (name "Net-(U23D-Y)") (class "Default")
      (node (ref "U23") (pin "8") (pinfunction "Y_8") (pintype "output"))
      (node (ref "U25") (pin "1") (pinfunction "~{OE}1_1") (pintype "input"))
      (node (ref "U25") (pin "19") (pinfunction "~{OE}2_19") (pintype "input"))
    )
    (net (code "107") (name "Net-(U23E-Y)") (class "Default")
      (node (ref "U23") (pin "10") (pinfunction "Y_10") (pintype "output"))
      (node (ref "U26") (pin "3") (pinfunction "~{E}_3") (pintype "input"))
    )
    (net (code "108") (name "Net-(U23F-Y)") (class "Default")
      (node (ref "U23") (pin "12") (pinfunction "Y_12") (pintype "output"))
      (node (ref "U27") (pin "3") (pinfunction "~{E}_3") (pintype "input"))
    )
    (net (code "109") (name "Net-(U24A-CX)") (class "Default")
      (node (ref "C17") (pin "1") (pinfunction "1_1") (pintype "passive"))
      (node (ref "U24") (pin "14") (pinfunction "CX_14") (pintype "passive"))
    )
    (net (code "110") (name "Net-(U24A-CX{slash}RX)") (class "Default")
      (node (ref "C17") (pin "2") (pinfunction "2_2") (pintype "passive"))
      (node (ref "R63") (pin "2") (pinfunction "2_2") (pintype "passive"))
      (node (ref "U24") (pin "15") (pinfunction "CX/RX_15") (pintype "passive"))
    )
    (net (code "111") (name "Net-(U24A-~{CLR})") (class "Default")
      (node (ref "R61") (pin "2") (pinfunction "2_2") (pintype "passive"))
      (node (ref "U24") (pin "3") (pinfunction "~{CLR}_3") (pintype "input"))
    )
    (net (code "112") (name "Net-(U24B-CX)") (class "Default")
      (node (ref "C18") (pin "1") (pinfunction "1_1") (pintype "passive"))
      (node (ref "U24") (pin "6") (pinfunction "CX_6") (pintype "passive"))
    )
    (net (code "113") (name "Net-(U24B-CX{slash}RX)") (class "Default")
      (node (ref "C18") (pin "2") (pinfunction "2_2") (pintype "passive"))
      (node (ref "R64") (pin "2") (pinfunction "2_2") (pintype "passive"))
      (node (ref "U24") (pin "7") (pinfunction "CX/RX_7") (pintype "passive"))
    )
    (net (code "114") (name "Net-(U24B-~{CLR})") (class "Default")
      (node (ref "R62") (pin "1") (pinfunction "1_1") (pintype "passive"))
      (node (ref "U24") (pin "11") (pinfunction "~{CLR}_11") (pintype "input"))
    )
    (net (code "115") (name "VCC") (class "Default")
      (node (ref "R41") (pin "1") (pinfunction "1_1") (pintype "passive"))
      (node (ref "R59") (pin "2") (pinfunction "2_2") (pintype "passive"))
      (node (ref "R61") (pin "1") (pinfunction "1_1") (pintype "passive"))
      (node (ref "R62") (pin "2") (pinfunction "2_2") (pintype "passive"))
      (node (ref "R63") (pin "1") (pinfunction "1_1") (pintype "passive"))
      (node (ref "R64") (pin "1") (pinfunction "1_1") (pintype "passive"))
      (node (ref "R72") (pin "1") (pinfunction "1_1") (pintype "passive"))
      (node (ref "R75") (pin "1") (pinfunction "1_1") (pintype "passive"))
      (node (ref "R76") (pin "1") (pinfunction "1_1") (pintype "passive"))
      (node (ref "U15") (pin "16") (pinfunction "VCC_16") (pintype "power_in"))
      (node (ref "U16") (pin "16") (pinfunction "VCC_16") (pintype "power_in"))
      (node (ref "U17") (pin "16") (pinfunction "VCC_16") (pintype "power_in"))
      (node (ref "U18") (pin "16") (pinfunction "VCC_16") (pintype "power_in"))
      (node (ref "U19") (pin "20") (pinfunction "VCC_20") (pintype "power_in"))
      (node (ref "U20") (pin "20") (pinfunction "VCC_20") (pintype "power_in"))
      (node (ref "U21") (pin "14") (pinfunction "VCC_14") (pintype "power_in"))
      (node (ref "U22") (pin "5") (pinfunction "VCC_5") (pintype "power_in"))
      (node (ref "U23") (pin "14") (pinfunction "VCC_14") (pintype "power_in"))
      (node (ref "U24") (pin "16") (pinfunction "VCC_16") (pintype "power_in"))
      (node (ref "U25") (pin "20") (pinfunction "VCC_20") (pintype "power_in"))
      (node (ref "U26") (pin "5") (pinfunction "VCC_5") (pintype "power_in"))
      (node (ref "U27") (pin "5") (pinfunction "VCC_5") (pintype "power_in"))
    )
    (net (code "116") (name "unconnected-(J2-Pad6)") (class "Default")
      (node (ref "J2") (pin "6") (pinfunction "6_6") (pintype "passive"))
    )
    (net (code "117") (name "unconnected-(J2-Pad16)") (class "Default")
      (node (ref "J2") (pin "16") (pinfunction "16_16") (pintype "passive"))
    )
    (net (code "118") (name "unconnected-(J2-Pad17)") (class "Default")
      (node (ref "J2") (pin "17") (pinfunction "17_17") (pintype "passive"))
    )
    (net (code "119") (name "unconnected-(J2-Pad18)") (class "Default")
      (node (ref "J2") (pin "18") (pinfunction "18_18") (pintype "passive"))
    )
    (net (code "120") (name "unconnected-(J2-Pad33)") (class "Default")
      (node (ref "J2") (pin "33") (pinfunction "33_33") (pintype "passive"))
    )
    (net (code "121") (name "unconnected-(J2-Pad34)") (class "Default")
      (node (ref "J2") (pin "34") (pinfunction "34_34") (pintype "passive"))
    )
    (net (code "122") (name "unconnected-(J2-Pad35)") (class "Default")
      (node (ref "J2") (pin "35") (pinfunction "35_35") (pintype "passive"))
    )
    (net (code "123") (name "unconnected-(J2-Pad37)") (class "Default")
      (node (ref "J2") (pin "37") (pinfunction "37_37") (pintype "passive"))
    )
    (net (code "124") (name "unconnected-(U18-~{BO}-Pad13)") (class "Default")
      (node (ref "U18") (pin "13") (pinfunction "~{BO}_13") (pintype "output"))
    )
    (net (code "125") (name "unconnected-(U18-~{CO}-Pad12)") (class "Default")
      (node (ref "U18") (pin "12") (pinfunction "~{CO}_12") (pintype "output"))
    )
    (net (code "126") (name "unconnected-(U21C-Y-Pad8)") (class "Default")
      (node (ref "U21") (pin "8") (pinfunction "Y_8") (pintype "output"))
    )
    (net (code "127") (name "unconnected-(U21D-Y-Pad11)") (class "Default")
      (node (ref "U21") (pin "11") (pinfunction "Y_11") (pintype "output"))
    )
    (net (code "128") (name "unconnected-(U24A-Q-Pad13)") (class "Default")
      (node (ref "U24") (pin "13") (pinfunction "Q_13") (pintype "output"))
    )
    (net (code "129") (name "unconnected-(U24B-Q-Pad5)") (class "Default")
      (node (ref "U24") (pin "5") (pinfunction "Q_5") (pintype "output"))
    )
  )
)
